# supply5v.net
KiCad netlist of a schematic drawn in EAGLE
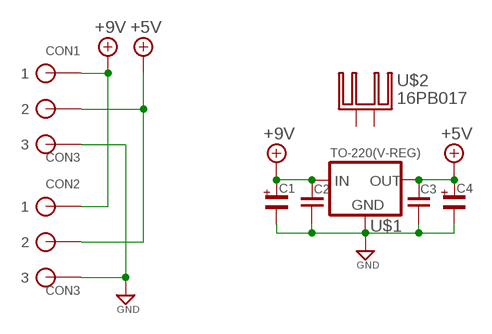
[diagram p0: schematic, sheet 1]

(export (version "E")
  (design (tool "Eeschema 10.0.6"))
  (components
    (comp (ref "C1")
      (value "コンデンサ(電解)E2.5-5")
      (footprint "eagle-import:D=1,φ=5")
      (libsource (lib "eagle-import") (part "コンデンサ(電解)E2.5-5"))
    )
    (comp (ref "C2")
      (value "(コンデンサ)セラミック050-024X044")
      (footprint "eagle-import:C050-024X044")
      (libsource (lib "eagle-import") (part "(コンデンサ)セラミック050-024X044"))
    )
    (comp (ref "C3")
      (value "(コンデンサ)セラミック050-024X044")
      (footprint "eagle-import:C050-024X044")
      (libsource (lib "eagle-import") (part "(コンデンサ)セラミック050-024X044"))
    )
    (comp (ref "C4")
      (value "コンデンサ(電解)E2.5-5")
      (footprint "eagle-import:D=1,φ=5")
      (libsource (lib "eagle-import") (part "コンデンサ(電解)E2.5-5"))
    )
    (comp (ref "CON1")
      (value "CON3")
      (footprint "eagle-import:CON3")
      (libsource (lib "eagle-import") (part "CON3"))
    )
    (comp (ref "CON2")
      (value "CON3")
      (footprint "eagle-import:CON3")
      (libsource (lib "eagle-import") (part "CON3"))
    )
    (comp (ref "U$1")
      (value "TO-220(V-REG)")
      (footprint "eagle-import:TO-220")
      (libsource (lib "eagle-import") (part "TO-220(V-REG)"))
    )
    (comp (ref "U$2")
      (value "16PB017")
      (footprint "eagle-import:16PB017")
      (libsource (lib "eagle-import") (part "16PB017"))
    )
  )
  (nets
    (net (code "1") (name "+5V") (class "Default")
      (node (ref "C3") (pin "1") (pinfunction "1_1") (pintype "passive"))
      (node (ref "C4") (pin "+") (pinfunction "+_+") (pintype "passive"))
      (node (ref "CON1") (pin "P$2") (pinfunction "2_P$2") (pintype "bidirectional"))
      (node (ref "CON2") (pin "P$2") (pinfunction "2_P$2") (pintype "bidirectional"))
      (node (ref "U$1") (pin "3") (pinfunction "OUT_3") (pintype "passive"))
    )
    (net (code "2") (name "+9V") (class "Default")
      (node (ref "C1") (pin "+") (pinfunction "+_+") (pintype "passive"))
      (node (ref "C2") (pin "1") (pinfunction "1_1") (pintype "passive"))
      (node (ref "CON1") (pin "P$1") (pinfunction "1_P$1") (pintype "bidirectional"))
      (node (ref "CON2") (pin "P$1") (pinfunction "1_P$1") (pintype "bidirectional"))
      (node (ref "U$1") (pin "2") (pinfunction "IN_2") (pintype "input"))
    )
    (net (code "3") (name "GND") (class "Default")
      (node (ref "C1") (pin "-") (pinfunction "-_-") (pintype "passive"))
      (node (ref "C2") (pin "2") (pinfunction "2_2") (pintype "passive"))
      (node (ref "C3") (pin "2") (pinfunction "2_2") (pintype "passive"))
      (node (ref "C4") (pin "-") (pinfunction "-_-") (pintype "passive"))
      (node (ref "CON1") (pin "P$3") (pinfunction "3_P$3") (pintype "bidirectional"))
      (node (ref "CON2") (pin "P$3") (pinfunction "3_P$3") (pintype "bidirectional"))
      (node (ref "U$1") (pin "1") (pinfunction "GND_1") (pintype "input"))
    )
    (net (code "4") (name "unconnected-(U$2-K-PadP$1)") (class "Default")
      (node (ref "U$2") (pin "P$1") (pinfunction "K_P$1") (pintype "passive"))
    )
    (net (code "5") (name "unconnected-(U$2-K-PadP$2)") (class "Default")
      (node (ref "U$2") (pin "P$2") (pinfunction "K_P$2") (pintype "passive"))
    )
  )
)
